# TIRA_LEDS_RGB.net
KiCad netlist of a schematic drawn in EAGLE
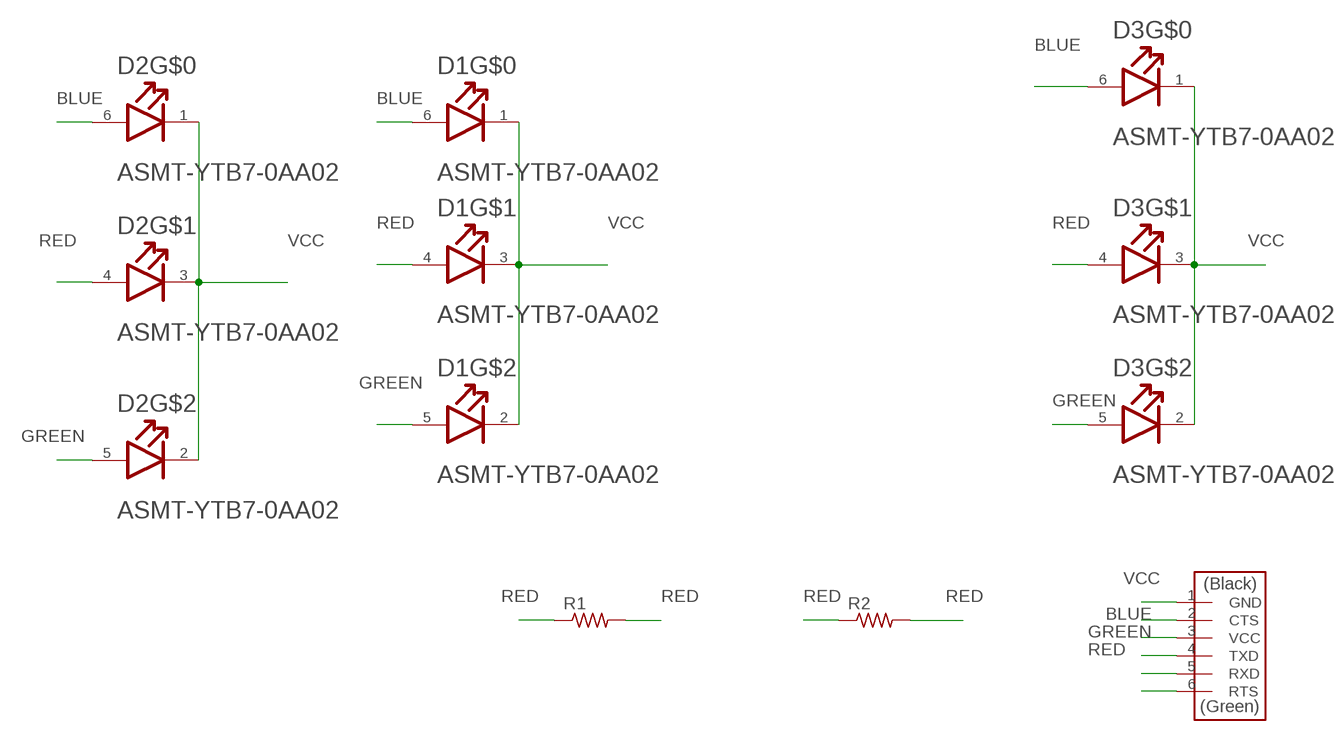
[diagram p0: schematic, sheet 1]

(export (version "E")
  (design (tool "Eeschema 10.0.6"))
  (components
    (comp (ref "D1")
      (value "BROADCOM_ASMT-YTB7-0AA02BROADCOM_ASMT-YTB7-0AA02_0_0")
      (footprint "eagle-import:BROADCOM_ASMT-YTB7-0AA02_0")
      (fields
        (field (name "DIGIKEY_PART_NUMBER") "516-3132-1-ND")
        (field (name "MF") "Broadcom")
        (field (name "MOUSER_PART_NUMBER") "630-ASMT-YTB7-0AA02")
      )
      (libsource (lib "eagle-import") (part "BROADCOM_ASMT-YTB7-0AA02BROADCOM_ASMT-YTB7-0AA02_0_0"))
    )
    (comp (ref "D2")
      (value "BROADCOM_ASMT-YTB7-0AA02BROADCOM_ASMT-YTB7-0AA02_0_0")
      (footprint "eagle-import:BROADCOM_ASMT-YTB7-0AA02_0")
      (fields
        (field (name "DIGIKEY_PART_NUMBER") "516-3132-1-ND")
        (field (name "MF") "Broadcom")
        (field (name "MOUSER_PART_NUMBER") "630-ASMT-YTB7-0AA02")
      )
      (libsource (lib "eagle-import") (part "BROADCOM_ASMT-YTB7-0AA02BROADCOM_ASMT-YTB7-0AA02_0_0"))
    )
    (comp (ref "D3")
      (value "BROADCOM_ASMT-YTB7-0AA02BROADCOM_ASMT-YTB7-0AA02_0_0")
      (footprint "eagle-import:BROADCOM_ASMT-YTB7-0AA02_0")
      (fields
        (field (name "DIGIKEY_PART_NUMBER") "516-3132-1-ND")
        (field (name "MF") "Broadcom")
        (field (name "MOUSER_PART_NUMBER") "630-ASMT-YTB7-0AA02")
      )
      (libsource (lib "eagle-import") (part "BROADCOM_ASMT-YTB7-0AA02BROADCOM_ASMT-YTB7-0AA02_0_0"))
    )
    (comp (ref "R1")
      (value "R1206FAB")
      (footprint "eagle-import:R1206FAB")
      (libsource (lib "eagle-import") (part "R1206FAB"))
    )
    (comp (ref "R2")
      (value "R1206FAB")
      (footprint "eagle-import:R1206FAB")
      (libsource (lib "eagle-import") (part "R1206FAB"))
    )
    (comp (ref "U$1")
      (value "CONN_06_FTDI-SMD-HEADER")
      (footprint "eagle-import:1X06SMD")
      (libsource (lib "eagle-import") (part "CONN_06_FTDI-SMD-HEADER"))
    )
  )
  (nets
    (net (code "1") (name "/BLUE") (class "Default")
      (node (ref "D1") (pin "6") (pinfunction "ANODE(BLUE)_6") (pintype "passive"))
      (node (ref "D2") (pin "6") (pinfunction "ANODE(BLUE)_6") (pintype "passive"))
      (node (ref "D3") (pin "6") (pinfunction "ANODE(BLUE)_6") (pintype "passive"))
      (node (ref "U$1") (pin "2") (pinfunction "CTS_2") (pintype "bidirectional"))
    )
    (net (code "2") (name "/GREEN") (class "Default")
      (node (ref "D1") (pin "5") (pinfunction "ANODE(GREEN)_5") (pintype "passive"))
      (node (ref "D2") (pin "5") (pinfunction "ANODE(GREEN)_5") (pintype "passive"))
      (node (ref "D3") (pin "5") (pinfunction "ANODE(GREEN)_5") (pintype "passive"))
      (node (ref "U$1") (pin "3") (pinfunction "VCC_3") (pintype "bidirectional"))
    )
    (net (code "3") (name "/RED") (class "Default")
      (node (ref "D1") (pin "4") (pinfunction "ANODE(RED)_4") (pintype "passive"))
      (node (ref "D2") (pin "4") (pinfunction "ANODE(RED)_4") (pintype "passive"))
      (node (ref "D3") (pin "4") (pinfunction "ANODE(RED)_4") (pintype "passive"))
      (node (ref "R1") (pin "1") (pinfunction "1_1") (pintype "passive"))
      (node (ref "R1") (pin "2") (pinfunction "2_2") (pintype "passive"))
      (node (ref "R2") (pin "1") (pinfunction "1_1") (pintype "passive"))
      (node (ref "R2") (pin "2") (pinfunction "2_2") (pintype "passive"))
      (node (ref "U$1") (pin "4") (pinfunction "TXD_4") (pintype "bidirectional"))
    )
    (net (code "4") (name "/VCC") (class "Default")
      (node (ref "D1") (pin "1") (pinfunction "CATHODE(BLUE)_1") (pintype "passive"))
      (node (ref "D1") (pin "2") (pinfunction "CATHODE(GREEN)_2") (pintype "passive"))
      (node (ref "D1") (pin "3") (pinfunction "CATHODE(RED)_3") (pintype "passive"))
      (node (ref "D2") (pin "1") (pinfunction "CATHODE(BLUE)_1") (pintype "passive"))
      (node (ref "D2") (pin "2") (pinfunction "CATHODE(GREEN)_2") (pintype "passive"))
      (node (ref "D2") (pin "3") (pinfunction "CATHODE(RED)_3") (pintype "passive"))
      (node (ref "D3") (pin "1") (pinfunction "CATHODE(BLUE)_1") (pintype "passive"))
      (node (ref "D3") (pin "2") (pinfunction "CATHODE(GREEN)_2") (pintype "passive"))
      (node (ref "D3") (pin "3") (pinfunction "CATHODE(RED)_3") (pintype "passive"))
      (node (ref "U$1") (pin "1") (pinfunction "GND_1") (pintype "bidirectional"))
    )
    (net (code "5") (name "unconnected-(U$1-RTS-Pad6)") (class "Default")
      (node (ref "U$1") (pin "6") (pinfunction "RTS_6") (pintype "bidirectional"))
    )
    (net (code "6") (name "unconnected-(U$1-RXD-Pad5)") (class "Default")
      (node (ref "U$1") (pin "5") (pinfunction "RXD_5") (pintype "bidirectional"))
    )
  )
)
